# TLI5012B_E1000_2Go_Kit.net
KiCad netlist of a schematic drawn in EAGLE
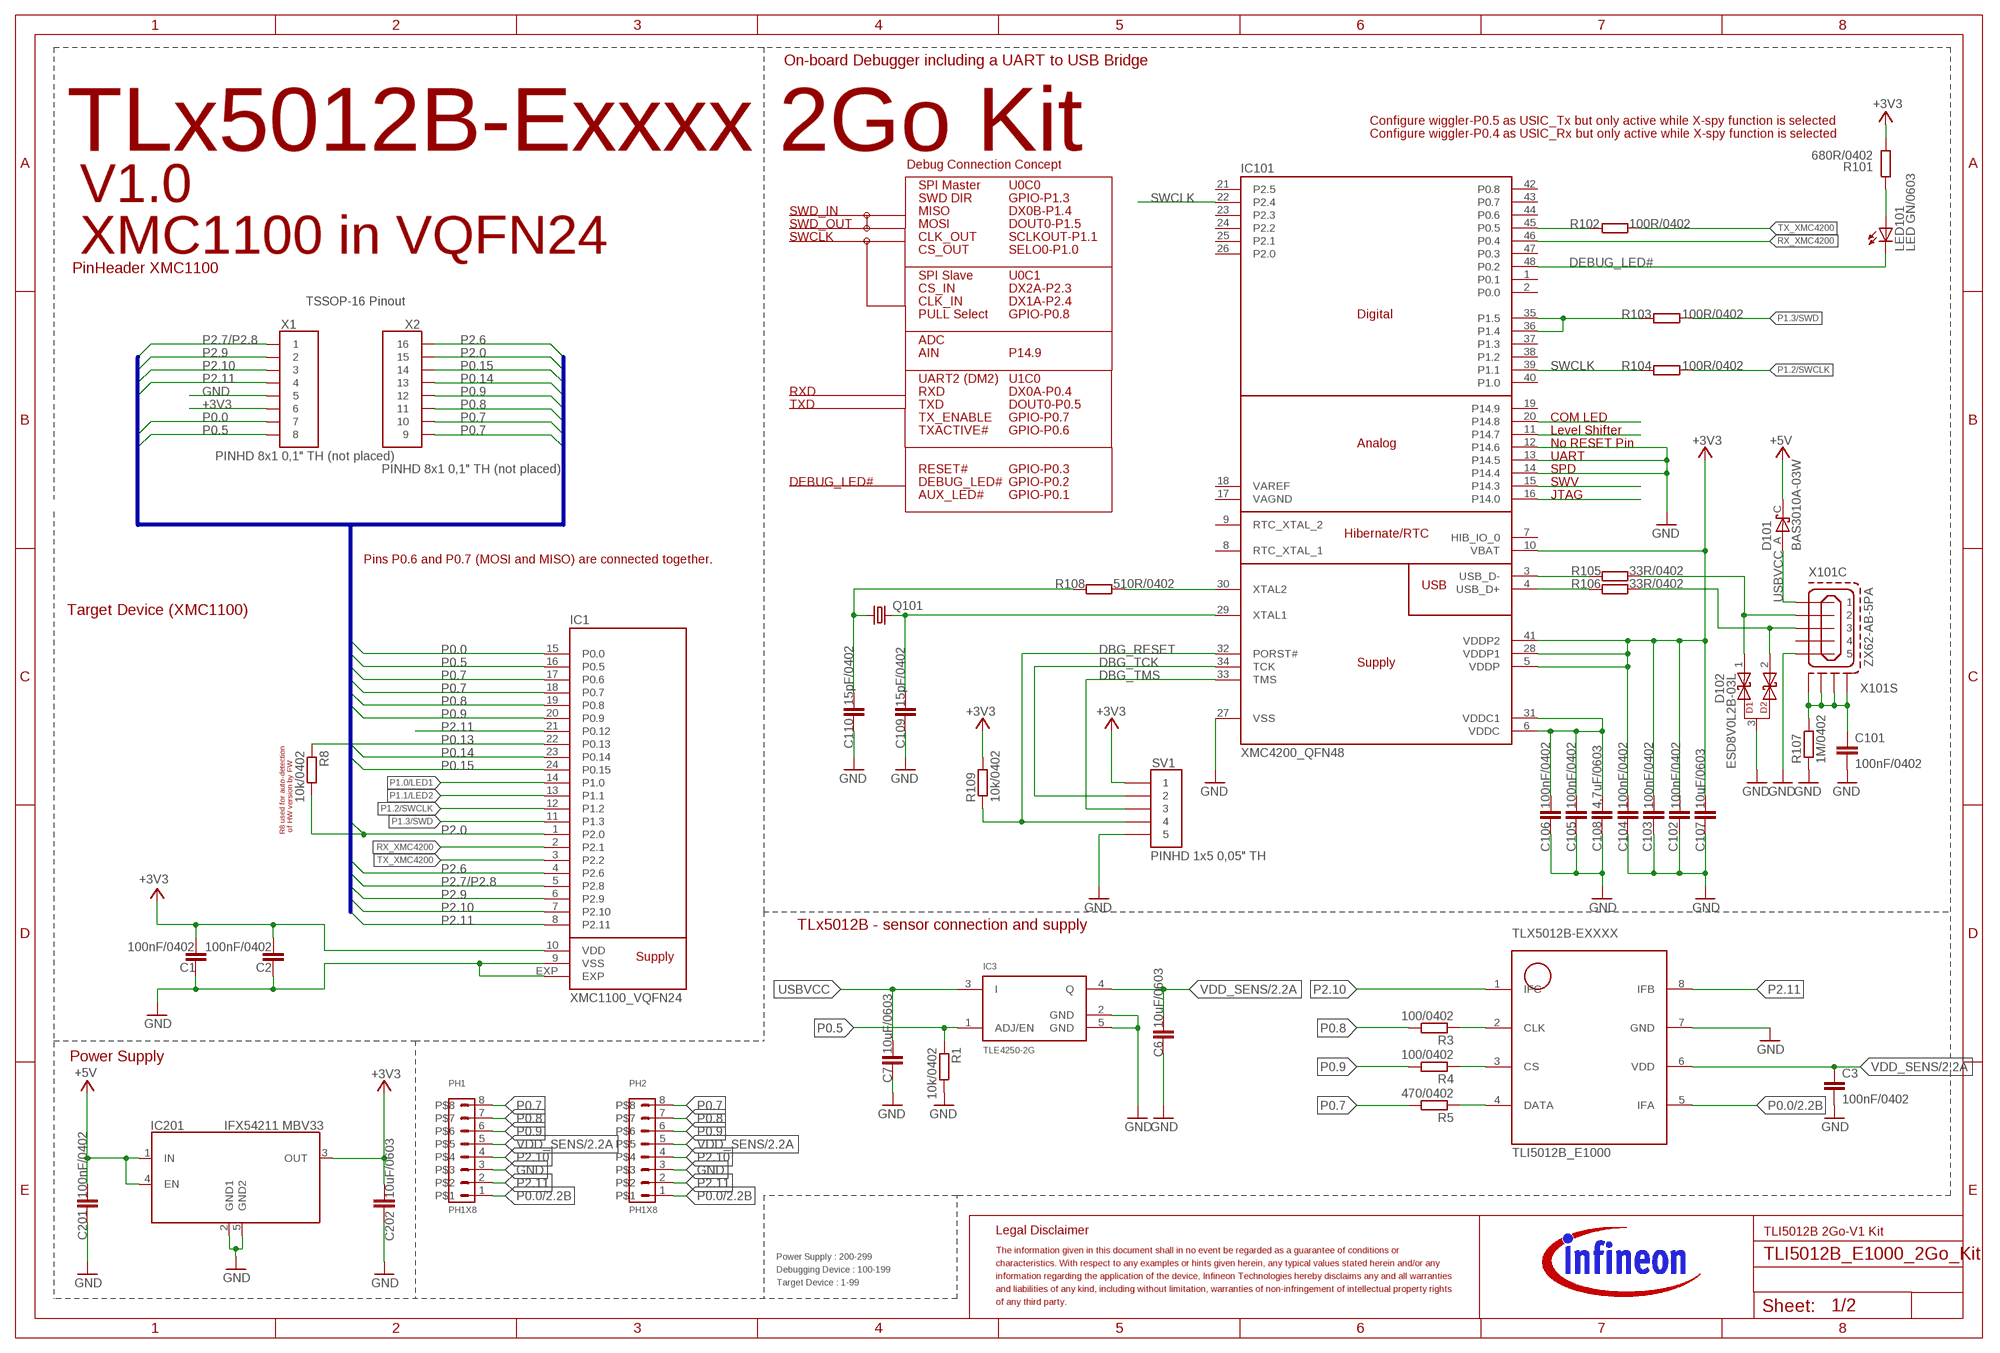
[diagram p0: schematic, sheet 1]
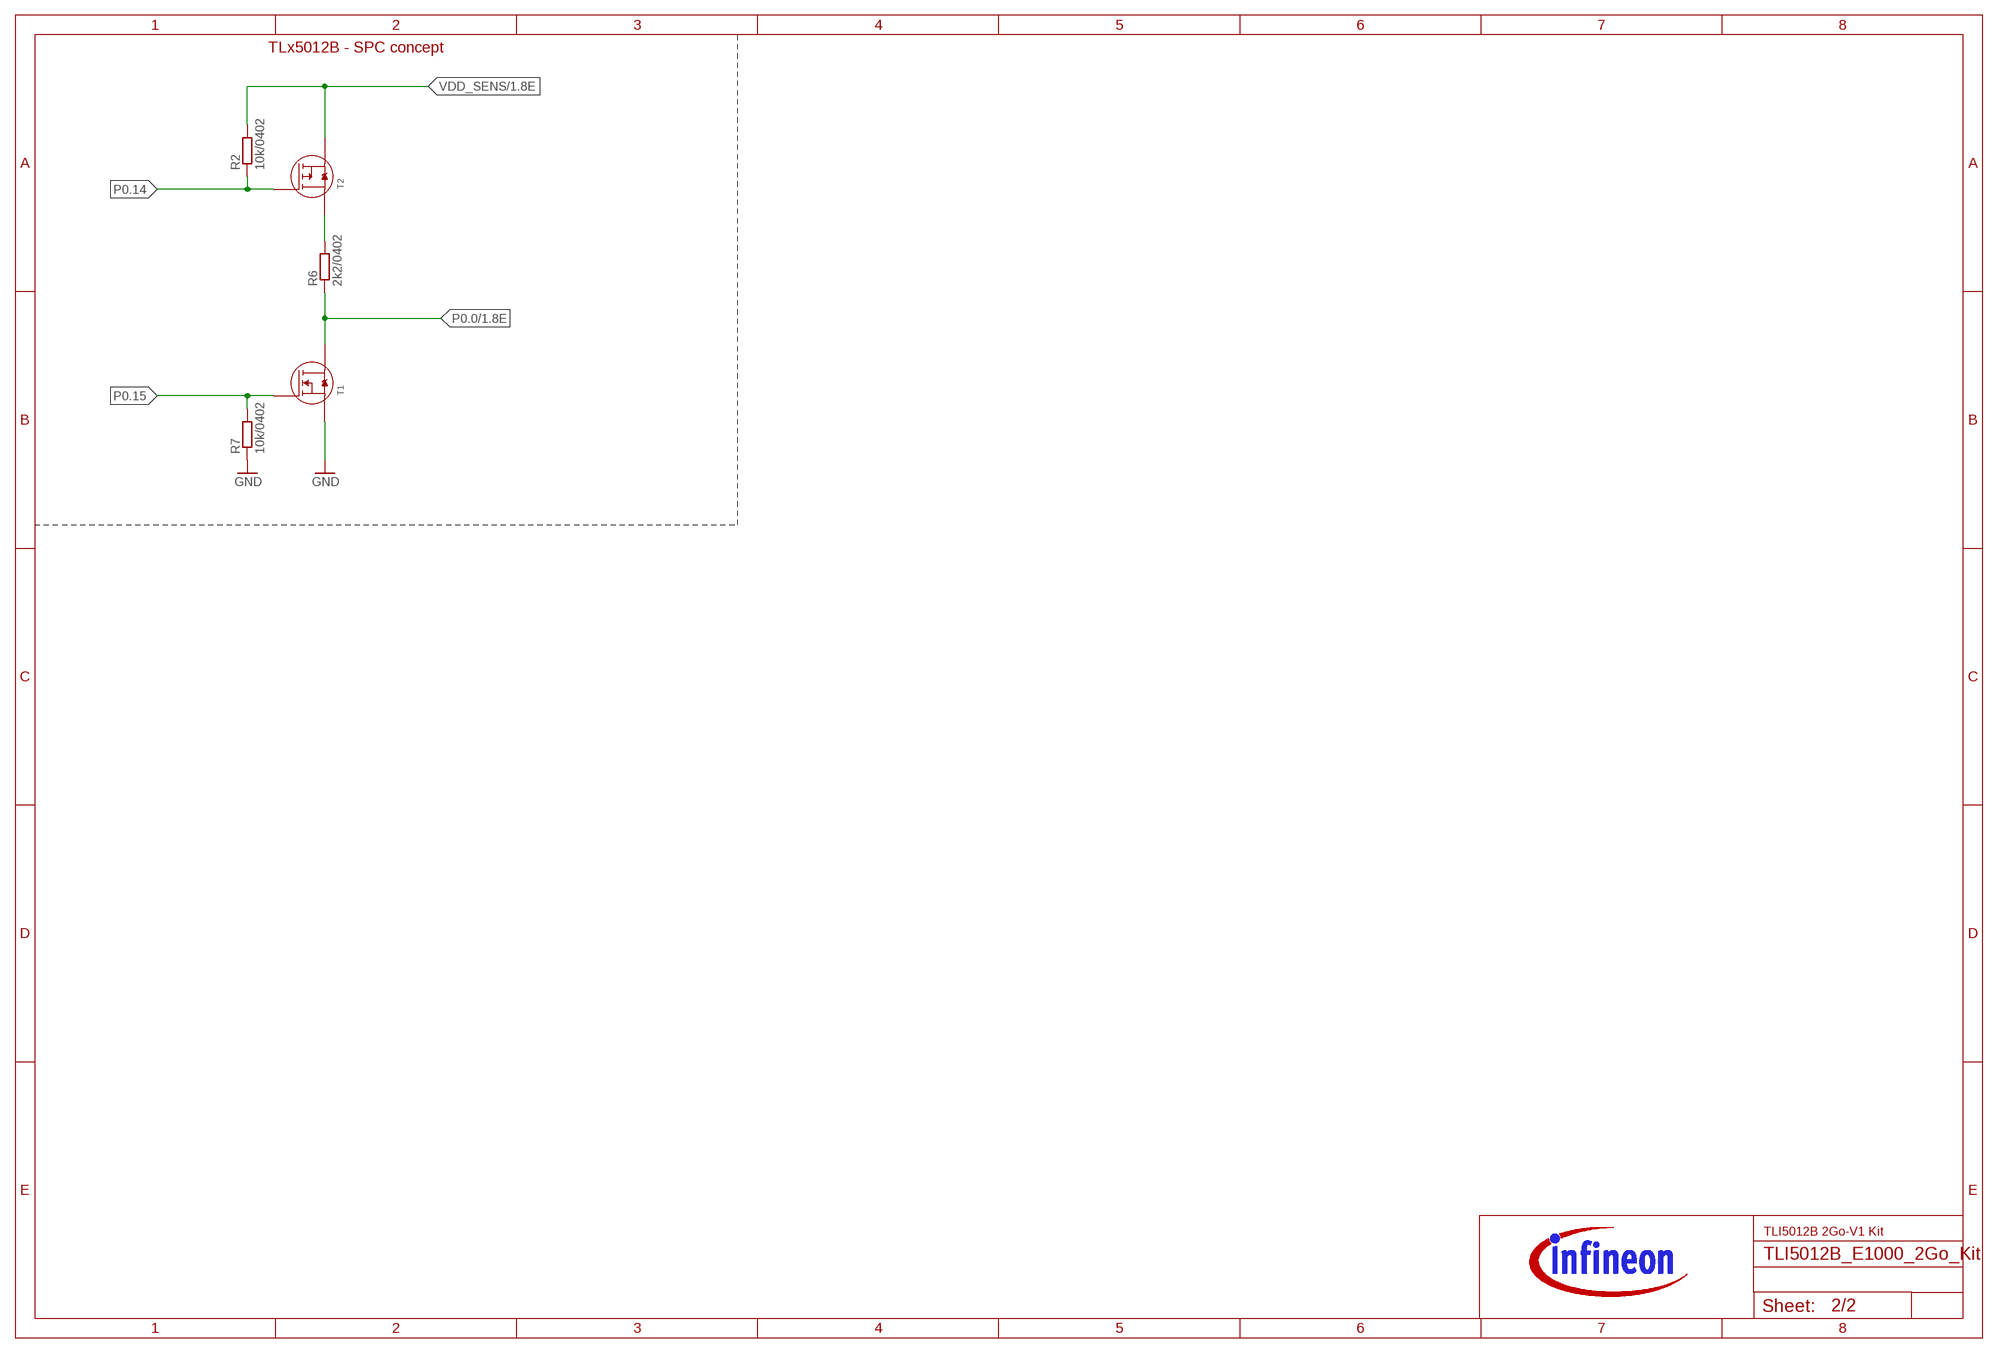
[diagram p1: schematic, sheet 2]

(export (version "E")
  (design (tool "Eeschema 10.0.6"))
  (components
    (comp (ref "R2")
      (value "10k/0402")
      (footprint "eagle-import:R0402")
      (libsource (lib "eagle-import") (part "R-EU_R0402"))
    )
    (comp (ref "R6")
      (value "2k2/0402")
      (footprint "eagle-import:R0402")
      (libsource (lib "eagle-import") (part "R-EU_R0402"))
    )
    (comp (ref "R7")
      (value "10k/0402")
      (footprint "eagle-import:R0402")
      (libsource (lib "eagle-import") (part "R-EU_R0402"))
    )
    (comp (ref "T1")
      (value "BSS138N")
      (footprint "eagle-import:INF-PG-SOT23_N_1PRIMARY")
      (libsource (lib "eagle-import") (part "BSS138N"))
    )
    (comp (ref "T2")
      (value "BSS84P")
      (footprint "eagle-import:INF-PG-SOT23_N_1PRIMARY")
      (libsource (lib "eagle-import") (part "BSS84P"))
    )
    (comp (ref "C1")
      (value "100nF/0402")
      (footprint "eagle-import:C0402")
      (libsource (lib "eagle-import") (part "C-EUC0402"))
    )
    (comp (ref "C2")
      (value "100nF/0402")
      (footprint "eagle-import:C0402")
      (libsource (lib "eagle-import") (part "C-EUC0402"))
    )
    (comp (ref "C3")
      (value "100nF/0402")
      (footprint "eagle-import:C0402")
      (libsource (lib "eagle-import") (part "C-EUC0402"))
    )
    (comp (ref "C6")
      (value "10uF/0603")
      (footprint "eagle-import:C0603")
      (libsource (lib "eagle-import") (part "C-EUC0603"))
    )
    (comp (ref "C7")
      (value "10uF/0603")
      (footprint "eagle-import:C0603")
      (libsource (lib "eagle-import") (part "C-EUC0603"))
    )
    (comp (ref "C101")
      (value "100nF/0402")
      (footprint "eagle-import:C0402")
      (libsource (lib "eagle-import") (part "C-EUC0402"))
    )
    (comp (ref "C102")
      (value "100nF/0402")
      (footprint "eagle-import:C0402")
      (libsource (lib "eagle-import") (part "C-EUC0402"))
    )
    (comp (ref "C103")
      (value "100nF/0402")
      (footprint "eagle-import:C0402")
      (libsource (lib "eagle-import") (part "C-EUC0402"))
    )
    (comp (ref "C104")
      (value "100nF/0402")
      (footprint "eagle-import:C0402")
      (libsource (lib "eagle-import") (part "C-EUC0402"))
    )
    (comp (ref "C105")
      (value "100nF/0402")
      (footprint "eagle-import:C0402")
      (libsource (lib "eagle-import") (part "C-EUC0402"))
    )
    (comp (ref "C106")
      (value "100nF/0402")
      (footprint "eagle-import:C0402")
      (libsource (lib "eagle-import") (part "C-EUC0402"))
    )
    (comp (ref "C107")
      (value "10uF/0603")
      (footprint "eagle-import:C0603")
      (libsource (lib "eagle-import") (part "C-EUC0603"))
    )
    (comp (ref "C108")
      (value "4,7uF/0603")
      (footprint "eagle-import:C0603")
      (libsource (lib "eagle-import") (part "C-EUC0603"))
    )
    (comp (ref "C109")
      (value "15pF/0402")
      (footprint "eagle-import:C0402")
      (libsource (lib "eagle-import") (part "C-EUC0402"))
    )
    (comp (ref "C110")
      (value "15pF/0402")
      (footprint "eagle-import:C0402")
      (libsource (lib "eagle-import") (part "C-EUC0402"))
    )
    (comp (ref "C201")
      (value "100nF/0402")
      (footprint "eagle-import:C0402")
      (libsource (lib "eagle-import") (part "C-EUC0402"))
    )
    (comp (ref "C202")
      (value "10uF/0603")
      (footprint "eagle-import:C0603")
      (libsource (lib "eagle-import") (part "C-EUC0603"))
    )
    (comp (ref "D101")
      (value "BAS3010A-03W")
      (footprint "eagle-import:SOD323-R")
      (libsource (lib "eagle-import") (part "BAT60"))
    )
    (comp (ref "D102")
      (value "ESD8V0L2B-03L")
      (footprint "eagle-import:TSLP-3-1")
      (libsource (lib "eagle-import") (part "ESD8V0L2B-03L"))
    )
    (comp (ref "IC1")
      (value "XMC1100_VQFN24")
      (footprint "eagle-import:VQFN24")
      (libsource (lib "eagle-import") (part "XMC1100_VQFN24"))
    )
    (comp (ref "IC3")
      (value "TLE4250-2G")
      (footprint "eagle-import:PG-SCT595")
      (libsource (lib "eagle-import") (part "TLE4250-2G"))
    )
    (comp (ref "IC101")
      (value "XMC4200_QFN48")
      (footprint "eagle-import:QFN-48-7X7")
      (libsource (lib "eagle-import") (part "XMC4200_QFN48"))
    )
    (comp (ref "IC201")
      (value "IFX54211 MBV33")
      (footprint "eagle-import:SCT595_INFINEON")
      (libsource (lib "eagle-import") (part "TLS202B1MBV"))
    )
    (comp (ref "LED101")
      (value "LED GN/0603")
      (footprint "eagle-import:CHIPLED_0603")
      (libsource (lib "eagle-import") (part "LEDCHIPLED_0603"))
    )
    (comp (ref "PH1")
      (value "PH1X8")
      (footprint "eagle-import:PH005-1-8")
      (libsource (lib "eagle-import") (part "PH1X8"))
    )
    (comp (ref "PH2")
      (value "PH1X8")
      (footprint "eagle-import:PH005-1-8")
      (libsource (lib "eagle-import") (part "PH1X8"))
    )
    (comp (ref "Q101")
      (value "NX3225_2")
      (footprint "eagle-import:32X25_4PAD")
      (libsource (lib "eagle-import") (part "NX3225_2"))
    )
    (comp (ref "R1")
      (value "10k/0402")
      (footprint "eagle-import:R0402")
      (libsource (lib "eagle-import") (part "R-EU_R0402"))
    )
    (comp (ref "R3")
      (value "100/0402")
      (footprint "eagle-import:R0402")
      (libsource (lib "eagle-import") (part "R-EU_R0402"))
    )
    (comp (ref "R4")
      (value "100/0402")
      (footprint "eagle-import:R0402")
      (libsource (lib "eagle-import") (part "R-EU_R0402"))
    )
    (comp (ref "R5")
      (value "470/0402")
      (footprint "eagle-import:R0402")
      (libsource (lib "eagle-import") (part "R-EU_R0402"))
    )
    (comp (ref "R8")
      (value "10k/0402")
      (footprint "eagle-import:R0402")
      (libsource (lib "eagle-import") (part "R-EU_R0402"))
    )
    (comp (ref "R101")
      (value "680R/0402")
      (footprint "eagle-import:R0402")
      (libsource (lib "eagle-import") (part "R-EU_R0402"))
    )
    (comp (ref "R102")
      (value "100R/0402")
      (footprint "eagle-import:R0402")
      (libsource (lib "eagle-import") (part "R-EU_R0402"))
    )
    (comp (ref "R103")
      (value "100R/0402")
      (footprint "eagle-import:R0402")
      (libsource (lib "eagle-import") (part "R-EU_R0402"))
    )
    (comp (ref "R104")
      (value "100R/0402")
      (footprint "eagle-import:R0402")
      (libsource (lib "eagle-import") (part "R-EU_R0402"))
    )
    (comp (ref "R105")
      (value "33R/0402")
      (footprint "eagle-import:R0402")
      (libsource (lib "eagle-import") (part "R-EU_R0402"))
    )
    (comp (ref "R106")
      (value "33R/0402")
      (footprint "eagle-import:R0402")
      (libsource (lib "eagle-import") (part "R-EU_R0402"))
    )
    (comp (ref "R107")
      (value "1M/0402")
      (footprint "eagle-import:R0402")
      (libsource (lib "eagle-import") (part "R-EU_R06030402"))
    )
    (comp (ref "R108")
      (value "510R/0402")
      (footprint "eagle-import:R0402")
      (libsource (lib "eagle-import") (part "R-EU_R0402"))
    )
    (comp (ref "R109")
      (value "10k/0402")
      (footprint "eagle-import:R0402")
      (libsource (lib "eagle-import") (part "R-EU_R0402"))
    )
    (comp (ref "SV1")
      (value "PINHD 1x5 0,05\" TH")
      (footprint "eagle-import:PINHEAD_127")
      (libsource (lib "eagle-import") (part "PINHEAD_127"))
    )
    (comp (ref "TLX5012B-EXXXX")
      (value "TLI5012B_E1000")
      (footprint "eagle-import:INF-PG-DSO-8-16")
      (libsource (lib "eagle-import") (part "TLI5012B_E1000"))
    )
    (comp (ref "X1")
      (value "PINHD 8x1 0,1\" TH (not placed)")
      (footprint "eagle-import:PINHD_1X8_SP")
      (libsource (lib "eagle-import") (part "Pinhead_1x8_sp_V2_PINHD_1X8_SP"))
    )
    (comp (ref "X2")
      (value "PINHD 8x1 0,1\" TH (not placed)")
      (footprint "eagle-import:PINHD_1X8_SP")
      (libsource (lib "eagle-import") (part "PINHD_1X8_SP"))
    )
    (comp (ref "X101")
      (value "ZX62-AB-5PA")
      (footprint "eagle-import:ZX62-AB-5PA_MICRO-USB")
      (libsource (lib "eagle-import") (part "ZX62-AB-5PA_MICRO-USB"))
    )
  )
  (nets
    (net (code "1") (name "+3V3") (class "Default")
      (node (ref "C1") (pin "2") (pinfunction "2_2") (pintype "passive"))
      (node (ref "C102") (pin "1") (pinfunction "1_1") (pintype "passive"))
      (node (ref "C103") (pin "1") (pinfunction "1_1") (pintype "passive"))
      (node (ref "C104") (pin "1") (pinfunction "1_1") (pintype "passive"))
      (node (ref "C107") (pin "1") (pinfunction "1_1") (pintype "passive"))
      (node (ref "C2") (pin "2") (pinfunction "2_2") (pintype "passive"))
      (node (ref "C202") (pin "1") (pinfunction "1_1") (pintype "passive"))
      (node (ref "IC1") (pin "10") (pinfunction "VDD_10") (pintype "power_in"))
      (node (ref "IC101") (pin "10") (pinfunction "VBAT_10") (pintype "bidirectional"))
      (node (ref "IC101") (pin "28") (pinfunction "VDDP1_28") (pintype "bidirectional"))
      (node (ref "IC101") (pin "41") (pinfunction "VDDP2_41") (pintype "bidirectional"))
      (node (ref "IC101") (pin "5") (pinfunction "VDDP_5") (pintype "bidirectional"))
      (node (ref "IC201") (pin "3") (pinfunction "OUT_3") (pintype "output"))
      (node (ref "R101") (pin "1") (pinfunction "1_1") (pintype "passive"))
      (node (ref "R109") (pin "2") (pinfunction "2_2") (pintype "passive"))
      (node (ref "SV1") (pin "P$1") (pinfunction "1_P$1") (pintype "bidirectional"))
      (node (ref "X1") (pin "6") (pinfunction "P$6_6") (pintype "bidirectional"))
    )
    (net (code "2") (name "+5V") (class "Default")
      (node (ref "C201") (pin "1") (pinfunction "1_1") (pintype "passive"))
      (node (ref "D101") (pin "C") (pinfunction "C_C") (pintype "passive"))
      (node (ref "IC201") (pin "1") (pinfunction "IN_1") (pintype "input"))
      (node (ref "IC201") (pin "4") (pinfunction "EN_4") (pintype "input"))
    )
    (net (code "3") (name "DBG_RESET") (class "Default")
      (node (ref "IC101") (pin "32") (pinfunction "PORST#_32") (pintype "bidirectional"))
      (node (ref "R109") (pin "1") (pinfunction "1_1") (pintype "passive"))
      (node (ref "SV1") (pin "P$4") (pinfunction "4_P$4") (pintype "bidirectional"))
    )
    (net (code "4") (name "DBG_TCK") (class "Default")
      (node (ref "IC101") (pin "34") (pinfunction "TCK_34") (pintype "bidirectional"))
      (node (ref "SV1") (pin "P$2") (pinfunction "2_P$2") (pintype "bidirectional"))
    )
    (net (code "5") (name "DBG_TMS") (class "Default")
      (node (ref "IC101") (pin "33") (pinfunction "TMS_33") (pintype "bidirectional"))
      (node (ref "SV1") (pin "P$3") (pinfunction "3_P$3") (pintype "bidirectional"))
    )
    (net (code "6") (name "DEBUG_LED#") (class "Default")
      (node (ref "IC101") (pin "48") (pinfunction "P0.2_48") (pintype "bidirectional"))
      (node (ref "LED101") (pin "C") (pinfunction "C_C") (pintype "passive"))
    )
    (net (code "7") (name "GND") (class "Default")
      (node (ref "C1") (pin "1") (pinfunction "1_1") (pintype "passive"))
      (node (ref "C101") (pin "2") (pinfunction "2_2") (pintype "passive"))
      (node (ref "C102") (pin "2") (pinfunction "2_2") (pintype "passive"))
      (node (ref "C103") (pin "2") (pinfunction "2_2") (pintype "passive"))
      (node (ref "C104") (pin "2") (pinfunction "2_2") (pintype "passive"))
      (node (ref "C105") (pin "2") (pinfunction "2_2") (pintype "passive"))
      (node (ref "C106") (pin "2") (pinfunction "2_2") (pintype "passive"))
      (node (ref "C107") (pin "2") (pinfunction "2_2") (pintype "passive"))
      (node (ref "C108") (pin "2") (pinfunction "2_2") (pintype "passive"))
      (node (ref "C109") (pin "2") (pinfunction "2_2") (pintype "passive"))
      (node (ref "C110") (pin "2") (pinfunction "2_2") (pintype "passive"))
      (node (ref "C2") (pin "1") (pinfunction "1_1") (pintype "passive"))
      (node (ref "C201") (pin "2") (pinfunction "2_2") (pintype "passive"))
      (node (ref "C202") (pin "2") (pinfunction "2_2") (pintype "passive"))
      (node (ref "C3") (pin "2") (pinfunction "2_2") (pintype "passive"))
      (node (ref "C6") (pin "2") (pinfunction "2_2") (pintype "passive"))
      (node (ref "C7") (pin "2") (pinfunction "2_2") (pintype "passive"))
      (node (ref "D102") (pin "3") (pinfunction "3_3") (pintype "passive"))
      (node (ref "IC1") (pin "9") (pinfunction "VSS_9") (pintype "power_in"))
      (node (ref "IC1") (pin "EXP") (pinfunction "EXP_EXP") (pintype "power_in"))
      (node (ref "IC101") (pin "12") (pinfunction "P14.6_12") (pintype "bidirectional"))
      (node (ref "IC101") (pin "13") (pinfunction "P14.5_13") (pintype "bidirectional"))
      (node (ref "IC101") (pin "14") (pinfunction "P14.4_14") (pintype "bidirectional"))
      (node (ref "IC101") (pin "27") (pinfunction "VSS_27") (pintype "bidirectional"))
      (node (ref "IC201") (pin "2") (pinfunction "GND1_2") (pintype "power_in"))
      (node (ref "IC201") (pin "5") (pinfunction "GND2_5") (pintype "power_in"))
      (node (ref "IC3") (pin "2") (pinfunction "GND_2") (pintype "power_in"))
      (node (ref "IC3") (pin "5") (pinfunction "GND_5") (pintype "power_in"))
      (node (ref "PH1") (pin "3") (pinfunction "P$3_3") (pintype "bidirectional"))
      (node (ref "PH2") (pin "3") (pinfunction "P$3_3") (pintype "bidirectional"))
      (node (ref "R1") (pin "2") (pinfunction "2_2") (pintype "passive"))
      (node (ref "R107") (pin "1") (pinfunction "1_1") (pintype "passive"))
      (node (ref "R7") (pin "1") (pinfunction "1_1") (pintype "passive"))
      (node (ref "SV1") (pin "P$5") (pinfunction "5_P$5") (pintype "bidirectional"))
      (node (ref "T1") (pin "2") (pinfunction "S_2") (pintype "bidirectional"))
      (node (ref "TLX5012B-EXXXX") (pin "7") (pinfunction "GND_7") (pintype "bidirectional"))
      (node (ref "X1") (pin "5") (pinfunction "P$5_5") (pintype "bidirectional"))
      (node (ref "X101") (pin "5") (pinfunction "5_5") (pintype "passive"))
    )
    (net (code "8") (name "Net-(C101-Pad1)") (class "Default")
      (node (ref "C101") (pin "1") (pinfunction "1_1") (pintype "passive"))
      (node (ref "R107") (pin "2") (pinfunction "2_2") (pintype "passive"))
      (node (ref "X101") (pin "S1") (pinfunction "S1_S1") (pintype "passive"))
      (node (ref "X101") (pin "S2") (pinfunction "S2_S2") (pintype "passive"))
      (node (ref "X101") (pin "S3") (pinfunction "S3_S3") (pintype "passive"))
      (node (ref "X101") (pin "S4") (pinfunction "S4_S4") (pintype "passive"))
    )
    (net (code "9") (name "Net-(C110-Pad1)") (class "Default")
      (node (ref "C110") (pin "1") (pinfunction "1_1") (pintype "passive"))
      (node (ref "Q101") (pin "1") (pinfunction "1_1") (pintype "passive"))
      (node (ref "R108") (pin "1") (pinfunction "1_1") (pintype "passive"))
    )
    (net (code "10") (name "Net-(D102-Pad1)") (class "Default")
      (node (ref "D102") (pin "1") (pinfunction "1_1") (pintype "passive"))
      (node (ref "R105") (pin "2") (pinfunction "2_2") (pintype "passive"))
      (node (ref "X101") (pin "2") (pinfunction "2_2") (pintype "passive"))
    )
    (net (code "11") (name "Net-(D102-Pad2)") (class "Default")
      (node (ref "D102") (pin "2") (pinfunction "2_2") (pintype "passive"))
      (node (ref "R106") (pin "2") (pinfunction "2_2") (pintype "passive"))
      (node (ref "X101") (pin "3") (pinfunction "3_3") (pintype "passive"))
    )
    (net (code "12") (name "Net-(IC101-P0.5)") (class "Default")
      (node (ref "IC101") (pin "45") (pinfunction "P0.5_45") (pintype "bidirectional"))
      (node (ref "R102") (pin "1") (pinfunction "1_1") (pintype "passive"))
    )
    (net (code "13") (name "Net-(IC101-P1.4)") (class "Default")
      (node (ref "IC101") (pin "35") (pinfunction "P1.5_35") (pintype "bidirectional"))
      (node (ref "IC101") (pin "36") (pinfunction "P1.4_36") (pintype "bidirectional"))
      (node (ref "R103") (pin "1") (pinfunction "1_1") (pintype "passive"))
    )
    (net (code "14") (name "Net-(IC101-USB_D+)") (class "Default")
      (node (ref "IC101") (pin "4") (pinfunction "USB_D+_4") (pintype "bidirectional"))
      (node (ref "R106") (pin "1") (pinfunction "1_1") (pintype "passive"))
    )
    (net (code "15") (name "Net-(IC101-USB_D-)") (class "Default")
      (node (ref "IC101") (pin "3") (pinfunction "USB_D-_3") (pintype "bidirectional"))
      (node (ref "R105") (pin "1") (pinfunction "1_1") (pintype "passive"))
    )
    (net (code "16") (name "Net-(IC101-VDDC)") (class "Default")
      (node (ref "C105") (pin "1") (pinfunction "1_1") (pintype "passive"))
      (node (ref "C106") (pin "1") (pinfunction "1_1") (pintype "passive"))
      (node (ref "C108") (pin "1") (pinfunction "1_1") (pintype "passive"))
      (node (ref "IC101") (pin "31") (pinfunction "VDDC1_31") (pintype "bidirectional"))
      (node (ref "IC101") (pin "6") (pinfunction "VDDC_6") (pintype "bidirectional"))
    )
    (net (code "17") (name "Net-(IC101-XTAL1)") (class "Default")
      (node (ref "C109") (pin "1") (pinfunction "1_1") (pintype "passive"))
      (node (ref "IC101") (pin "29") (pinfunction "XTAL1_29") (pintype "bidirectional"))
      (node (ref "Q101") (pin "3") (pinfunction "2_3") (pintype "passive"))
    )
    (net (code "18") (name "Net-(IC101-XTAL2)") (class "Default")
      (node (ref "IC101") (pin "30") (pinfunction "XTAL2_30") (pintype "bidirectional"))
      (node (ref "R108") (pin "2") (pinfunction "2_2") (pintype "passive"))
    )
    (net (code "19") (name "Net-(LED101-PadA)") (class "Default")
      (node (ref "LED101") (pin "A") (pinfunction "A_A") (pintype "passive"))
      (node (ref "R101") (pin "2") (pinfunction "2_2") (pintype "passive"))
    )
    (net (code "20") (name "Net-(T2-D)") (class "Default")
      (node (ref "R6") (pin "2") (pinfunction "2_2") (pintype "passive"))
      (node (ref "T2") (pin "3") (pinfunction "D_3") (pintype "bidirectional"))
    )
    (net (code "21") (name "Net-(TLX5012B-EXXXX-CLK)") (class "Default")
      (node (ref "R3") (pin "1") (pinfunction "1_1") (pintype "passive"))
      (node (ref "TLX5012B-EXXXX") (pin "2") (pinfunction "CLK_2") (pintype "bidirectional"))
    )
    (net (code "22") (name "Net-(TLX5012B-EXXXX-CS)") (class "Default")
      (node (ref "R4") (pin "1") (pinfunction "1_1") (pintype "passive"))
      (node (ref "TLX5012B-EXXXX") (pin "3") (pinfunction "CS_3") (pintype "bidirectional"))
    )
    (net (code "23") (name "Net-(TLX5012B-EXXXX-DATA)") (class "Default")
      (node (ref "R5") (pin "1") (pinfunction "1_1") (pintype "passive"))
      (node (ref "TLX5012B-EXXXX") (pin "4") (pinfunction "DATA_4") (pintype "bidirectional"))
    )
    (net (code "24") (name "P0.0") (class "Default")
      (node (ref "IC1") (pin "15") (pinfunction "P0.0_15") (pintype "bidirectional"))
      (node (ref "PH1") (pin "1") (pinfunction "P$1_1") (pintype "bidirectional"))
      (node (ref "PH2") (pin "1") (pinfunction "P$1_1") (pintype "bidirectional"))
      (node (ref "R6") (pin "1") (pinfunction "1_1") (pintype "passive"))
      (node (ref "T1") (pin "3") (pinfunction "D_3") (pintype "bidirectional"))
      (node (ref "TLX5012B-EXXXX") (pin "5") (pinfunction "IFA_5") (pintype "bidirectional"))
      (node (ref "X1") (pin "7") (pinfunction "P$7_7") (pintype "bidirectional"))
    )
    (net (code "25") (name "P0.5") (class "Default")
      (node (ref "IC1") (pin "16") (pinfunction "P0.5_16") (pintype "bidirectional"))
      (node (ref "IC3") (pin "1") (pinfunction "ADJ/EN_1") (pintype "input"))
      (node (ref "R1") (pin "1") (pinfunction "1_1") (pintype "passive"))
      (node (ref "X1") (pin "8") (pinfunction "P$8_8") (pintype "bidirectional"))
    )
    (net (code "26") (name "P0.7") (class "Default")
      (node (ref "IC1") (pin "17") (pinfunction "P0.6_17") (pintype "bidirectional"))
      (node (ref "IC1") (pin "18") (pinfunction "P0.7_18") (pintype "bidirectional"))
      (node (ref "PH1") (pin "8") (pinfunction "P$8_8") (pintype "bidirectional"))
      (node (ref "PH2") (pin "8") (pinfunction "P$8_8") (pintype "bidirectional"))
      (node (ref "R5") (pin "2") (pinfunction "2_2") (pintype "passive"))
      (node (ref "X2") (pin "7") (pinfunction "P$7_7") (pintype "bidirectional"))
      (node (ref "X2") (pin "8") (pinfunction "P$8_8") (pintype "bidirectional"))
    )
    (net (code "27") (name "P0.8") (class "Default")
      (node (ref "IC1") (pin "19") (pinfunction "P0.8_19") (pintype "bidirectional"))
      (node (ref "PH1") (pin "7") (pinfunction "P$7_7") (pintype "bidirectional"))
      (node (ref "PH2") (pin "7") (pinfunction "P$7_7") (pintype "bidirectional"))
      (node (ref "R3") (pin "2") (pinfunction "2_2") (pintype "passive"))
      (node (ref "X2") (pin "6") (pinfunction "P$6_6") (pintype "bidirectional"))
    )
    (net (code "28") (name "P0.9") (class "Default")
      (node (ref "IC1") (pin "20") (pinfunction "P0.9_20") (pintype "bidirectional"))
      (node (ref "PH1") (pin "6") (pinfunction "P$6_6") (pintype "bidirectional"))
      (node (ref "PH2") (pin "6") (pinfunction "P$6_6") (pintype "bidirectional"))
      (node (ref "R4") (pin "2") (pinfunction "2_2") (pintype "passive"))
      (node (ref "X2") (pin "5") (pinfunction "P$5_5") (pintype "bidirectional"))
    )
    (net (code "29") (name "P0.13") (class "Default")
      (node (ref "IC1") (pin "22") (pinfunction "P0.13_22") (pintype "bidirectional"))
      (node (ref "R8") (pin "1") (pinfunction "1_1") (pintype "passive"))
    )
    (net (code "30") (name "P0.14") (class "Default")
      (node (ref "IC1") (pin "23") (pinfunction "P0.14_23") (pintype "bidirectional"))
      (node (ref "R2") (pin "1") (pinfunction "1_1") (pintype "passive"))
      (node (ref "T2") (pin "1") (pinfunction "G_1") (pintype "bidirectional"))
      (node (ref "X2") (pin "4") (pinfunction "P$4_4") (pintype "bidirectional"))
    )
    (net (code "31") (name "P0.15") (class "Default")
      (node (ref "IC1") (pin "24") (pinfunction "P0.15_24") (pintype "bidirectional"))
      (node (ref "R7") (pin "2") (pinfunction "2_2") (pintype "passive"))
      (node (ref "T1") (pin "1") (pinfunction "G_1") (pintype "bidirectional"))
      (node (ref "X2") (pin "3") (pinfunction "P$3_3") (pintype "bidirectional"))
    )
    (net (code "32") (name "P1.0{slash}LED1") (class "Default")
      (node (ref "IC1") (pin "14") (pinfunction "P1.0_14") (pintype "bidirectional"))
    )
    (net (code "33") (name "P1.1{slash}LED2") (class "Default")
      (node (ref "IC1") (pin "13") (pinfunction "P1.1_13") (pintype "bidirectional"))
    )
    (net (code "34") (name "P1.2{slash}SWCLK") (class "Default")
      (node (ref "IC1") (pin "12") (pinfunction "P1.2_12") (pintype "bidirectional"))
      (node (ref "R104") (pin "2") (pinfunction "2_2") (pintype "passive"))
    )
    (net (code "35") (name "P1.3{slash}SWD") (class "Default")
      (node (ref "IC1") (pin "11") (pinfunction "P1.3_11") (pintype "bidirectional"))
      (node (ref "R103") (pin "2") (pinfunction "2_2") (pintype "passive"))
    )
    (net (code "36") (name "P2.0") (class "Default")
      (node (ref "IC1") (pin "1") (pinfunction "P2.0_1") (pintype "bidirectional"))
      (node (ref "R8") (pin "2") (pinfunction "2_2") (pintype "passive"))
      (node (ref "X2") (pin "2") (pinfunction "P$2_2") (pintype "bidirectional"))
    )
    (net (code "37") (name "P2.6") (class "Default")
      (node (ref "IC1") (pin "4") (pinfunction "P2.6_4") (pintype "bidirectional"))
      (node (ref "X2") (pin "1") (pinfunction "P$1_1") (pintype "bidirectional"))
    )
    (net (code "38") (name "P2.7{slash}P2.8") (class "Default")
      (node (ref "IC1") (pin "5") (pinfunction "P2.8_5") (pintype "bidirectional"))
      (node (ref "X1") (pin "P$1") (pinfunction "P$1_P$1") (pintype "bidirectional"))
    )
    (net (code "39") (name "P2.9") (class "Default")
      (node (ref "IC1") (pin "6") (pinfunction "P2.9_6") (pintype "bidirectional"))
      (node (ref "X1") (pin "2") (pinfunction "P$2_2") (pintype "bidirectional"))
    )
    (net (code "40") (name "P2.10") (class "Default")
      (node (ref "IC1") (pin "7") (pinfunction "P2.10_7") (pintype "bidirectional"))
      (node (ref "PH1") (pin "4") (pinfunction "P$4_4") (pintype "bidirectional"))
      (node (ref "PH2") (pin "4") (pinfunction "P$4_4") (pintype "bidirectional"))
      (node (ref "TLX5012B-EXXXX") (pin "1") (pinfunction "IFC_1") (pintype "bidirectional"))
      (node (ref "X1") (pin "3") (pinfunction "P$3_3") (pintype "bidirectional"))
    )
    (net (code "41") (name "P2.11") (class "Default")
      (node (ref "IC1") (pin "21") (pinfunction "P0.12_21") (pintype "bidirectional"))
      (node (ref "IC1") (pin "8") (pinfunction "P2.11_8") (pintype "bidirectional"))
      (node (ref "PH1") (pin "2") (pinfunction "P$2_2") (pintype "bidirectional"))
      (node (ref "PH2") (pin "2") (pinfunction "P$2_2") (pintype "bidirectional"))
      (node (ref "TLX5012B-EXXXX") (pin "8") (pinfunction "IFB_8") (pintype "bidirectional"))
      (node (ref "X1") (pin "4") (pinfunction "P$4_4") (pintype "bidirectional"))
    )
    (net (code "42") (name "RX_XMC4200") (class "Default")
      (node (ref "IC1") (pin "2") (pinfunction "P2.1_2") (pintype "bidirectional"))
      (node (ref "IC101") (pin "46") (pinfunction "P0.4_46") (pintype "bidirectional"))
    )
    (net (code "43") (name "SWCLK") (class "Default")
      (node (ref "IC101") (pin "22") (pinfunction "P2.4_22") (pintype "bidirectional"))
      (node (ref "IC101") (pin "39") (pinfunction "P1.1_39") (pintype "bidirectional"))
      (node (ref "R104") (pin "1") (pinfunction "1_1") (pintype "passive"))
    )
    (net (code "44") (name "TX_XMC4200") (class "Default")
      (node (ref "IC1") (pin "3") (pinfunction "P2.2_3") (pintype "bidirectional"))
      (node (ref "R102") (pin "2") (pinfunction "2_2") (pintype "passive"))
    )
    (net (code "45") (name "USBVCC") (class "Default")
      (node (ref "C7") (pin "1") (pinfunction "1_1") (pintype "passive"))
      (node (ref "D101") (pin "A") (pinfunction "A_A") (pintype "passive"))
      (node (ref "IC3") (pin "3") (pinfunction "I_3") (pintype "power_in"))
      (node (ref "X101") (pin "1") (pinfunction "1_1") (pintype "passive"))
    )
    (net (code "46") (name "VDD_SENS") (class "Default")
      (node (ref "C3") (pin "1") (pinfunction "1_1") (pintype "passive"))
      (node (ref "C6") (pin "1") (pinfunction "1_1") (pintype "passive"))
      (node (ref "IC3") (pin "4") (pinfunction "Q_4") (pintype "power_in"))
      (node (ref "PH1") (pin "5") (pinfunction "P$5_5") (pintype "bidirectional"))
      (node (ref "PH2") (pin "5") (pinfunction "P$5_5") (pintype "bidirectional"))
      (node (ref "R2") (pin "2") (pinfunction "2_2") (pintype "passive"))
      (node (ref "T2") (pin "2") (pinfunction "S_2") (pintype "bidirectional"))
      (node (ref "TLX5012B-EXXXX") (pin "6") (pinfunction "VDD_6") (pintype "bidirectional"))
    )
    (net (code "47") (name "unconnected-(IC101-HIB_IO_0-Pad7)") (class "Default")
      (node (ref "IC101") (pin "7") (pinfunction "HIB_IO_0_7") (pintype "bidirectional"))
    )
    (net (code "48") (name "unconnected-(IC101-P0.0-Pad2)") (class "Default")
      (node (ref "IC101") (pin "2") (pinfunction "P0.0_2") (pintype "bidirectional"))
    )
    (net (code "49") (name "unconnected-(IC101-P0.1-Pad1)") (class "Default")
      (node (ref "IC101") (pin "1") (pinfunction "P0.1_1") (pintype "bidirectional"))
    )
    (net (code "50") (name "unconnected-(IC101-P0.3-Pad47)") (class "Default")
      (node (ref "IC101") (pin "47") (pinfunction "P0.3_47") (pintype "bidirectional"))
    )
    (net (code "51") (name "unconnected-(IC101-P0.6-Pad44)") (class "Default")
      (node (ref "IC101") (pin "44") (pinfunction "P0.6_44") (pintype "bidirectional"))
    )
    (net (code "52") (name "unconnected-(IC101-P0.7-Pad43)") (class "Default")
      (node (ref "IC101") (pin "43") (pinfunction "P0.7_43") (pintype "bidirectional"))
    )
    (net (code "53") (name "unconnected-(IC101-P0.8-Pad42)") (class "Default")
      (node (ref "IC101") (pin "42") (pinfunction "P0.8_42") (pintype "bidirectional"))
    )
    (net (code "54") (name "unconnected-(IC101-P1.0-Pad40)") (class "Default")
      (node (ref "IC101") (pin "40") (pinfunction "P1.0_40") (pintype "bidirectional"))
    )
    (net (code "55") (name "unconnected-(IC101-P1.2-Pad38)") (class "Default")
      (node (ref "IC101") (pin "38") (pinfunction "P1.2_38") (pintype "bidirectional"))
    )
    (net (code "56") (name "unconnected-(IC101-P1.3-Pad37)") (class "Default")
      (node (ref "IC101") (pin "37") (pinfunction "P1.3_37") (pintype "bidirectional"))
    )
    (net (code "57") (name "unconnected-(IC101-P2.0-Pad26)") (class "Default")
      (node (ref "IC101") (pin "26") (pinfunction "P2.0_26") (pintype "bidirectional"))
    )
    (net (code "58") (name "unconnected-(IC101-P2.1-Pad25)") (class "Default")
      (node (ref "IC101") (pin "25") (pinfunction "P2.1_25") (pintype "bidirectional"))
    )
    (net (code "59") (name "unconnected-(IC101-P2.2-Pad24)") (class "Default")
      (node (ref "IC101") (pin "24") (pinfunction "P2.2_24") (pintype "bidirectional"))
    )
    (net (code "60") (name "unconnected-(IC101-P2.3-Pad23)") (class "Default")
      (node (ref "IC101") (pin "23") (pinfunction "P2.3_23") (pintype "bidirectional"))
    )
    (net (code "61") (name "unconnected-(IC101-P2.5-Pad21)") (class "Default")
      (node (ref "IC101") (pin "21") (pinfunction "P2.5_21") (pintype "bidirectional"))
    )
    (net (code "62") (name "unconnected-(IC101-P14.0-Pad16)") (class "Default")
      (node (ref "IC101") (pin "16") (pinfunction "P14.0_16") (pintype "bidirectional"))
    )
    (net (code "63") (name "unconnected-(IC101-P14.3-Pad15)") (class "Default")
      (node (ref "IC101") (pin "15") (pinfunction "P14.3_15") (pintype "bidirectional"))
    )
    (net (code "64") (name "unconnected-(IC101-P14.7-Pad11)") (class "Default")
      (node (ref "IC101") (pin "11") (pinfunction "P14.7_11") (pintype "bidirectional"))
    )
    (net (code "65") (name "unconnected-(IC101-P14.8-Pad20)") (class "Default")
      (node (ref "IC101") (pin "20") (pinfunction "P14.8_20") (pintype "bidirectional"))
    )
    (net (code "66") (name "unconnected-(IC101-P14.9-Pad19)") (class "Default")
      (node (ref "IC101") (pin "19") (pinfunction "P14.9_19") (pintype "bidirectional"))
    )
    (net (code "67") (name "unconnected-(IC101-RTC_XTAL_1-Pad8)") (class "Default")
      (node (ref "IC101") (pin "8") (pinfunction "RTC_XTAL_1_8") (pintype "bidirectional"))
    )
    (net (code "68") (name "unconnected-(IC101-RTC_XTAL_2-Pad9)") (class "Default")
      (node (ref "IC101") (pin "9") (pinfunction "RTC_XTAL_2_9") (pintype "bidirectional"))
    )
    (net (code "69") (name "unconnected-(IC101-VAGND-Pad17)") (class "Default")
      (node (ref "IC101") (pin "17") (pinfunction "VAGND_17") (pintype "bidirectional"))
    )
    (net (code "70") (name "unconnected-(IC101-VAREF-Pad18)") (class "Default")
      (node (ref "IC101") (pin "18") (pinfunction "VAREF_18") (pintype "bidirectional"))
    )
    (net (code "71") (name "unconnected-(X101-Pad4)") (class "Default")
      (node (ref "X101") (pin "4") (pinfunction "4_4") (pintype "passive"))
    )
  )
)
